# ledboard_smallcon_vert.net
KiCad netlist of a schematic drawn in EAGLE
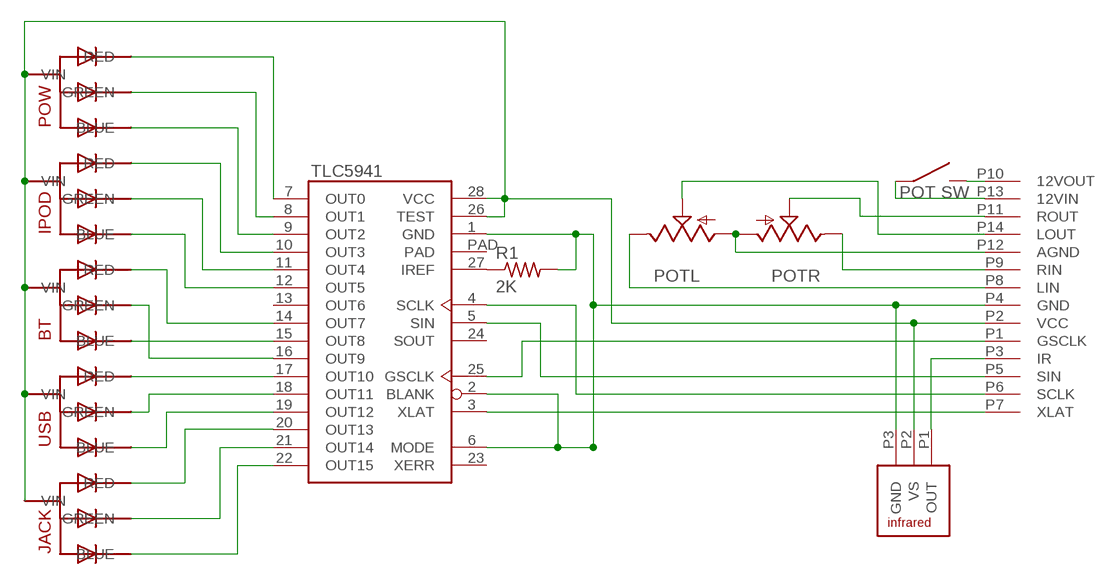
[diagram p0: schematic, sheet 1]

(export (version "E")
  (design (tool "Eeschema 10.0.6"))
  (components
    (comp (ref "BT")
      (value "5MMRGBLEDBENT")
      (footprint "eagle-import:BENTLED")
      (libsource (lib "eagle-import") (part "5MMRGBLEDBENT"))
    )
    (comp (ref "IPOD")
      (value "5MMRGBLEDBENT")
      (footprint "eagle-import:BENTLED")
      (libsource (lib "eagle-import") (part "5MMRGBLEDBENT"))
    )
    (comp (ref "IR")
      (value "TSOP323")
      (footprint "eagle-import:TSOP323")
      (libsource (lib "eagle-import") (part "TSOP323"))
    )
    (comp (ref "JACK")
      (value "5MMRGBLEDBENT")
      (footprint "eagle-import:BENTLED")
      (libsource (lib "eagle-import") (part "5MMRGBLEDBENT"))
    )
    (comp (ref "POT")
      (value "ALPS_RK0971221Z0N")
      (footprint "eagle-import:ALPS_RK0971221Z0X")
      (libsource (lib "eagle-import") (part "ALPS_RK0971221Z0N"))
    )
    (comp (ref "POW")
      (value "5MMRGBLEDBENT")
      (footprint "eagle-import:BENTLED")
      (libsource (lib "eagle-import") (part "5MMRGBLEDBENT"))
    )
    (comp (ref "R1")
      (value "2K")
      (footprint "eagle-import:0207_7")
      (libsource (lib "eagle-import") (part "R-US_0207/7"))
    )
    (comp (ref "U$1")
      (value "TLC5941")
      (footprint "eagle-import:HTSSOP28_POWERPAD")
      (libsource (lib "eagle-import") (part "TLC5941"))
    )
    (comp (ref "U$3")
      (value "CONNECTORSMALL2")
      (footprint "eagle-import:SMALL2")
      (libsource (lib "eagle-import") (part "CONNECTORSMALL2"))
    )
    (comp (ref "USB")
      (value "5MMRGBLEDBENT")
      (footprint "eagle-import:BENTLED")
      (libsource (lib "eagle-import") (part "5MMRGBLEDBENT"))
    )
  )
  (nets
    (net (code "1") (name "Net-(BT-BLUE)") (class "Default")
      (node (ref "BT") (pin "P$1") (pinfunction "BLUE_P$1") (pintype "bidirectional"))
      (node (ref "U$1") (pin "15") (pinfunction "OUT8_15") (pintype "output"))
    )
    (net (code "2") (name "Net-(BT-GREEN)") (class "Default")
      (node (ref "BT") (pin "P$2") (pinfunction "GREEN_P$2") (pintype "bidirectional"))
      (node (ref "U$1") (pin "16") (pinfunction "OUT9_16") (pintype "output"))
    )
    (net (code "3") (name "Net-(BT-RED)") (class "Default")
      (node (ref "BT") (pin "P$4") (pinfunction "RED_P$4") (pintype "bidirectional"))
      (node (ref "U$1") (pin "14") (pinfunction "OUT7_14") (pintype "output"))
    )
    (net (code "4") (name "Net-(BT-VIN)") (class "Default")
      (node (ref "BT") (pin "P$3") (pinfunction "VIN_P$3") (pintype "bidirectional"))
      (node (ref "IPOD") (pin "P$3") (pinfunction "VIN_P$3") (pintype "bidirectional"))
      (node (ref "IR") (pin "P2") (pinfunction "VS_P2") (pintype "bidirectional"))
      (node (ref "JACK") (pin "P$3") (pinfunction "VIN_P$3") (pintype "bidirectional"))
      (node (ref "POW") (pin "P$3") (pinfunction "VIN_P$3") (pintype "bidirectional"))
      (node (ref "U$1") (pin "26") (pinfunction "TEST_26") (pintype "bidirectional"))
      (node (ref "U$1") (pin "28") (pinfunction "VCC_28") (pintype "power_in"))
      (node (ref "U$3") (pin "P2") (pinfunction "VCC_P2") (pintype "bidirectional"))
      (node (ref "USB") (pin "P$3") (pinfunction "VIN_P$3") (pintype "bidirectional"))
    )
    (net (code "5") (name "Net-(IPOD-BLUE)") (class "Default")
      (node (ref "IPOD") (pin "P$1") (pinfunction "BLUE_P$1") (pintype "bidirectional"))
      (node (ref "U$1") (pin "12") (pinfunction "OUT5_12") (pintype "output"))
    )
    (net (code "6") (name "Net-(IPOD-GREEN)") (class "Default")
      (node (ref "IPOD") (pin "P$2") (pinfunction "GREEN_P$2") (pintype "bidirectional"))
      (node (ref "U$1") (pin "11") (pinfunction "OUT4_11") (pintype "output"))
    )
    (net (code "7") (name "Net-(IPOD-RED)") (class "Default")
      (node (ref "IPOD") (pin "P$4") (pinfunction "RED_P$4") (pintype "bidirectional"))
      (node (ref "U$1") (pin "10") (pinfunction "OUT3_10") (pintype "output"))
    )
    (net (code "8") (name "Net-(IR-GND)") (class "Default")
      (node (ref "IR") (pin "P3") (pinfunction "GND_P3") (pintype "bidirectional"))
      (node (ref "R1") (pin "2") (pinfunction "2_2") (pintype "passive"))
      (node (ref "U$1") (pin "1") (pinfunction "GND_1") (pintype "power_in"))
      (node (ref "U$1") (pin "2") (pinfunction "BLANK_2") (pintype "input"))
      (node (ref "U$1") (pin "6") (pinfunction "MODE_6") (pintype "bidirectional"))
      (node (ref "U$3") (pin "P4") (pinfunction "GND_P4") (pintype "bidirectional"))
    )
    (net (code "9") (name "Net-(IR-OUT)") (class "Default")
      (node (ref "IR") (pin "P1") (pinfunction "OUT_P1") (pintype "bidirectional"))
      (node (ref "U$3") (pin "P3") (pinfunction "IR_P3") (pintype "bidirectional"))
    )
    (net (code "10") (name "Net-(JACK-BLUE)") (class "Default")
      (node (ref "JACK") (pin "P$1") (pinfunction "BLUE_P$1") (pintype "bidirectional"))
      (node (ref "U$1") (pin "22") (pinfunction "OUT15_22") (pintype "output"))
    )
    (net (code "11") (name "Net-(JACK-GREEN)") (class "Default")
      (node (ref "JACK") (pin "P$2") (pinfunction "GREEN_P$2") (pintype "bidirectional"))
      (node (ref "U$1") (pin "21") (pinfunction "OUT14_21") (pintype "output"))
    )
    (net (code "12") (name "Net-(JACK-RED)") (class "Default")
      (node (ref "JACK") (pin "P$4") (pinfunction "RED_P$4") (pintype "bidirectional"))
      (node (ref "U$1") (pin "20") (pinfunction "OUT13_20") (pintype "output"))
    )
    (net (code "13") (name "Net-(POTB-1)") (class "Default")
      (node (ref "POT") (pin "G1") (pinfunction "1_G1") (pintype "passive"))
      (node (ref "POT") (pin "G2") (pinfunction "1_G2") (pintype "passive"))
      (node (ref "U$3") (pin "P12") (pinfunction "AGND_P12") (pintype "bidirectional"))
    )
    (net (code "14") (name "Net-(POTB-2)") (class "Default")
      (node (ref "POT") (pin "O1") (pinfunction "2_O1") (pintype "passive"))
      (node (ref "U$3") (pin "P14") (pinfunction "LOUT_P14") (pintype "bidirectional"))
    )
    (net (code "15") (name "Net-(POTB-3)") (class "Default")
      (node (ref "POT") (pin "I1") (pinfunction "3_I1") (pintype "passive"))
      (node (ref "U$3") (pin "P8") (pinfunction "LIN_P8") (pintype "bidirectional"))
    )
    (net (code "16") (name "Net-(POTC-2)") (class "Default")
      (node (ref "POT") (pin "O2") (pinfunction "2_O2") (pintype "passive"))
      (node (ref "U$3") (pin "P11") (pinfunction "ROUT_P11") (pintype "bidirectional"))
    )
    (net (code "17") (name "Net-(POTC-3)") (class "Default")
      (node (ref "POT") (pin "I2") (pinfunction "3_I2") (pintype "passive"))
      (node (ref "U$3") (pin "P9") (pinfunction "RIN_P9") (pintype "bidirectional"))
    )
    (net (code "18") (name "Net-(POW-BLUE)") (class "Default")
      (node (ref "POW") (pin "P$1") (pinfunction "BLUE_P$1") (pintype "bidirectional"))
      (node (ref "U$1") (pin "9") (pinfunction "OUT2_9") (pintype "output"))
    )
    (net (code "19") (name "Net-(POW-GREEN)") (class "Default")
      (node (ref "POW") (pin "P$2") (pinfunction "GREEN_P$2") (pintype "bidirectional"))
      (node (ref "U$1") (pin "8") (pinfunction "OUT1_8") (pintype "output"))
    )
    (net (code "20") (name "Net-(POW-RED)") (class "Default")
      (node (ref "POW") (pin "P$4") (pinfunction "RED_P$4") (pintype "bidirectional"))
      (node (ref "U$1") (pin "7") (pinfunction "OUT0_7") (pintype "output"))
    )
    (net (code "21") (name "Net-(U$1-GSCLK)") (class "Default")
      (node (ref "U$1") (pin "25") (pinfunction "GSCLK_25") (pintype "input"))
      (node (ref "U$3") (pin "P1") (pinfunction "GSCLK_P1") (pintype "bidirectional"))
    )
    (net (code "22") (name "Net-(U$1-IREF)") (class "Default")
      (node (ref "R1") (pin "1") (pinfunction "1_1") (pintype "passive"))
      (node (ref "U$1") (pin "27") (pinfunction "IREF_27") (pintype "input"))
    )
    (net (code "23") (name "Net-(U$1-OUT10)") (class "Default")
      (node (ref "U$1") (pin "17") (pinfunction "OUT10_17") (pintype "output"))
      (node (ref "USB") (pin "P$4") (pinfunction "RED_P$4") (pintype "bidirectional"))
    )
    (net (code "24") (name "Net-(U$1-OUT11)") (class "Default")
      (node (ref "U$1") (pin "18") (pinfunction "OUT11_18") (pintype "output"))
      (node (ref "USB") (pin "P$2") (pinfunction "GREEN_P$2") (pintype "bidirectional"))
    )
    (net (code "25") (name "Net-(U$1-OUT12)") (class "Default")
      (node (ref "U$1") (pin "19") (pinfunction "OUT12_19") (pintype "output"))
      (node (ref "USB") (pin "P$1") (pinfunction "BLUE_P$1") (pintype "bidirectional"))
    )
    (net (code "26") (name "Net-(U$1-SCLK)") (class "Default")
      (node (ref "U$1") (pin "4") (pinfunction "SCLK_4") (pintype "input"))
      (node (ref "U$3") (pin "P6") (pinfunction "SCLK_P6") (pintype "bidirectional"))
    )
    (net (code "27") (name "Net-(U$1-SIN)") (class "Default")
      (node (ref "U$1") (pin "5") (pinfunction "SIN_5") (pintype "input"))
      (node (ref "U$3") (pin "P5") (pinfunction "SIN_P5") (pintype "bidirectional"))
    )
    (net (code "28") (name "Net-(U$1-XLAT)") (class "Default")
      (node (ref "U$1") (pin "3") (pinfunction "XLAT_3") (pintype "input"))
      (node (ref "U$3") (pin "P7") (pinfunction "XLAT_P7") (pintype "bidirectional"))
    )
    (net (code "29") (name "Net-(U$3-12VIN)") (class "Default")
      (node (ref "POT") (pin "S1") (pinfunction "S1_S1") (pintype "power_in"))
      (node (ref "U$3") (pin "P13") (pinfunction "12VIN_P13") (pintype "bidirectional"))
    )
    (net (code "30") (name "Net-(U$3-12VOUT)") (class "Default")
      (node (ref "POT") (pin "S2") (pinfunction "S2_S2") (pintype "power_in"))
      (node (ref "U$3") (pin "P10") (pinfunction "12VOUT_P10") (pintype "bidirectional"))
    )
    (net (code "31") (name "unconnected-(U$1-OUT6-Pad13)") (class "Default")
      (node (ref "U$1") (pin "13") (pinfunction "OUT6_13") (pintype "output"))
    )
    (net (code "32") (name "unconnected-(U$1-PadPAD)") (class "Default")
      (node (ref "U$1") (pin "PAD") (pinfunction "PAD_PAD") (pintype "bidirectional"))
    )
    (net (code "33") (name "unconnected-(U$1-SOUT-Pad24)") (class "Default")
      (node (ref "U$1") (pin "24") (pinfunction "SOUT_24") (pintype "output"))
    )
    (net (code "34") (name "unconnected-(U$1-XERR-Pad23)") (class "Default")
      (node (ref "U$1") (pin "23") (pinfunction "XERR_23") (pintype "output"))
    )
  )
)
